# Air_SCH.net
KiCad netlist of a schematic drawn in Altium Designer
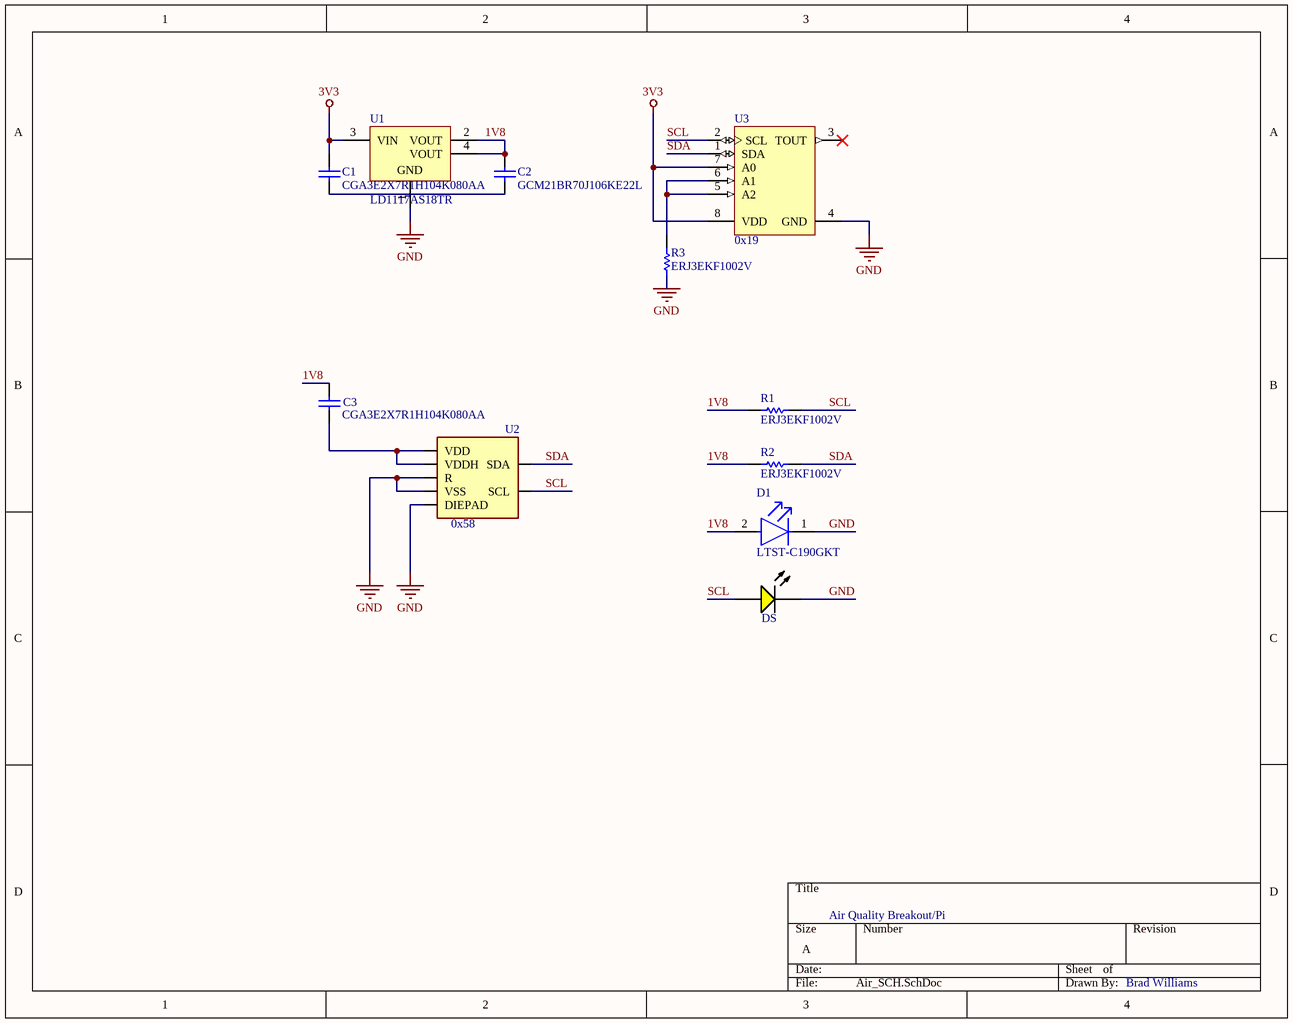
[diagram p0: Air_SCH.SchDoc]

(export (version "E")
  (design (tool "Eeschema 10.0.6"))
  (components
    (comp (ref "C1")
      (value "CGA3E2X7R1H104K080AA")
      (footprint "CAPC1608X90X20LL10")
      (description "Chip Capacitor, 0.1 uF, +/- 10%, 50 V, -55 to 125 degC, 0603 (1608 Metric), RoHS, Tape and Reel")
      (fields (field (name "VOLTAGE") "50V") (field (name "TOLERANCE") "10%"))
      (libsource (lib "Altium Content Vault") (part "CAP-NP-2"))
    )
    (comp (ref "C2")
      (value "GCM21BR70J106KE22L")
      (footprint "CAPC2013X140X45LL15T25")
      (fields (field (name "MANUFACTURER") "Murata"))
      (libsource (lib "Altium Content Vault") (part "CAP"))
    )
    (comp (ref "C3")
      (value "CGA3E2X7R1H104K080AA")
      (footprint "CAPC1608X90X20LL10")
      (description "Chip Capacitor, 0.1 uF, +/- 10%, 50 V, -55 to 125 degC, 0603 (1608 Metric), RoHS, Tape and Reel")
      (fields (field (name "VOLTAGE") "50V") (field (name "TOLERANCE") "10%"))
      (libsource (lib "Altium Content Vault") (part "CAP-NP-2"))
    )
    (comp (ref "D1")
      (value "LTST-C190GKT")
      (footprint "FP-LTST-C190GKT-MFG")
      (description "LED GREEN CLEAR CHIP SMD")
      (fields (field (name "VOLTAGE") "2V"))
      (libsource (lib "Altium Content Vault") (part "8706943c75ba83719d021d2fdc84c58"))
    )
    (comp (ref "DS")
      (value "HSMY-C190")
      (footprint "AVAG-HSMX-C190_V")
      (description "LED Uni-Color Yellow, 65 mW, 20 mA, -40 to 85 degC, 2-Pin SMD, RoHS, Tape and Reel")
      (fields (field (name "TOLERANCE") "1%"))
      (libsource (lib "Altium Content Vault") (part "LED-YELLOW-AK-2"))
    )
    (comp (ref "R1")
      (value "ERJ3EKF1002V")
      (footprint "RESC1609X55X30LL15T15")
      (description "Chip Resistor, 10 KOhm, +/- 1%, 0.1 W, -55 to 155 degC, 0603 (1608 Metric), RoHS, Tape and Reel")
      (fields (field (name "TOLERANCE") "1%") (field (name "MANUFACTURER") "Panasonic"))
      (libsource (lib "Altium Content Vault") (part "RES-2"))
    )
    (comp (ref "R2")
      (value "ERJ3EKF1002V")
      (footprint "RESC1609X55X30LL15T15")
      (description "Chip Resistor, 10 KOhm, +/- 1%, 0.1 W, -55 to 155 degC, 0603 (1608 Metric), RoHS, Tape and Reel")
      (fields (field (name "TOLERANCE") "1%") (field (name "MANUFACTURER") "Panasonic"))
      (libsource (lib "Altium Content Vault") (part "RES-2"))
    )
    (comp (ref "R3")
      (value "ERJ3EKF1002V")
      (footprint "RESC1609X55X30LL15T15")
      (description "Chip Resistor, 10 KOhm, +/- 1%, 0.1 W, -55 to 155 degC, 0603 (1608 Metric), RoHS, Tape and Reel")
      (fields (field (name "TOLERANCE") "1%") (field (name "MANUFACTURER") "Panasonic"))
      (libsource (lib "Altium Content Vault") (part "RES-2"))
    )
    (comp (ref "U1")
      (value "LD1117AS18TR")
      (footprint "SOT-223_L")
      (description "1A, Low Drop Positive Voltage Regulator, 1.8V, 4-Pin SOT-223, Tape and Reel")
      (libsource (lib "Altium Content Vault") (part "PM-REG-LD1117-SOT4"))
    )
    (comp (ref "U2")
      (value "0x58")
      (footprint "SGP30")
      (description "AIR QUALITY GAS SENSOR FOR VOC'S")
      (fields (field (name "MP") "SGP30") (field (name "MF") "Sensirion AG"))
      (libsource (lib "Brad Williams") (part "SGP30"))
    )
    (comp (ref "U3")
      (value "0x19")
      (footprint "MAXM-W8+2_L")
      (fields (field (name "GENERIC PART NUMBER") "DS1621") (field (name "PARTNUMBER") "DS1621V+"))
      (libsource (lib "Altium Content Vault") (part "DS1X21-X8XX"))
    )
  )
  (nets
    (net (code "1") (name "/1V8") (class "Default")
      (node (ref "C2") (pin "2") (pinfunction "2_2") (pintype "passive"))
      (node (ref "C3") (pin "2") (pinfunction "2_2") (pintype "passive"))
      (node (ref "D1") (pin "2") (pinfunction "A_2") (pintype "passive"))
      (node (ref "R1") (pin "2") (pinfunction "2_2") (pintype "passive"))
      (node (ref "R2") (pin "1") (pinfunction "1_1") (pintype "passive"))
      (node (ref "U1") (pin "2") (pinfunction "VOUT_2") (pintype "power_in"))
      (node (ref "U1") (pin "4") (pinfunction "VOUT_4") (pintype "power_in"))
    )
    (net (code "2") (name "/SCL") (class "Default")
      (node (ref "DS") (pin "1") (pinfunction "A_1") (pintype "passive"))
      (node (ref "R1") (pin "1") (pinfunction "1_1") (pintype "passive"))
      (node (ref "U2") (pin "6") (pinfunction "SCL_6") (pintype "bidirectional"))
      (node (ref "U3") (pin "2") (pinfunction "SCL_2") (pintype "bidirectional"))
    )
    (net (code "3") (name "/SDA") (class "Default")
      (node (ref "R2") (pin "2") (pinfunction "2_2") (pintype "passive"))
      (node (ref "U2") (pin "3") (pinfunction "SDA_3") (pintype "bidirectional"))
      (node (ref "U3") (pin "1") (pinfunction "SDA_1") (pintype "bidirectional"))
    )
    (net (code "4") (name "3V3") (class "Default")
      (node (ref "C1") (pin "2") (pinfunction "2_2") (pintype "passive"))
      (node (ref "U1") (pin "3") (pinfunction "VIN_3") (pintype "power_in"))
      (node (ref "U3") (pin "7") (pinfunction "A0_7") (pintype "input"))
      (node (ref "U3") (pin "8") (pinfunction "VDD_8") (pintype "power_in"))
    )
    (net (code "5") (name "GND") (class "Default")
      (node (ref "D1") (pin "1") (pinfunction "C_1") (pintype "passive"))
      (node (ref "DS") (pin "2") (pinfunction "K_2") (pintype "passive"))
      (node (ref "R3") (pin "2") (pinfunction "2_2") (pintype "passive"))
      (node (ref "U1") (pin "1") (pinfunction "GND_1") (pintype "power_in"))
      (node (ref "U2") (pin "2") (pinfunction "VSS_2") (pintype "bidirectional"))
      (node (ref "U2") (pin "4") (pinfunction "R_4") (pintype "bidirectional"))
      (node (ref "U2") (pin "DIEPAD") (pinfunction "DIEPAD_DIEPAD") (pintype "bidirectional"))
      (node (ref "U3") (pin "4") (pinfunction "GND_4") (pintype "power_in"))
    )
    (net (code "6") (name "Net-(C1-Pad1)") (class "Default")
      (node (ref "C1") (pin "1") (pinfunction "1_1") (pintype "passive"))
      (node (ref "C2") (pin "1") (pinfunction "1_1") (pintype "passive"))
    )
    (net (code "7") (name "Net-(U2-VDD)") (class "Default")
      (node (ref "C3") (pin "1") (pinfunction "1_1") (pintype "passive"))
      (node (ref "U2") (pin "1") (pinfunction "VDD_1") (pintype "bidirectional"))
      (node (ref "U2") (pin "5") (pinfunction "VDDH_5") (pintype "bidirectional"))
    )
    (net (code "8") (name "Net-(U3-A1)") (class "Default")
      (node (ref "R3") (pin "1") (pinfunction "1_1") (pintype "passive"))
      (node (ref "U3") (pin "5") (pinfunction "A2_5") (pintype "input"))
      (node (ref "U3") (pin "6") (pinfunction "A1_6") (pintype "input"))
    )
    (net (code "9") (name "unconnected-(U3-TOUT-Pad3)") (class "Default")
      (node (ref "U3") (pin "3") (pinfunction "TOUT_3") (pintype "output+no_connect"))
    )
  )
)
